# 2024-SS-ZT-2.net
KiCad netlist of a schematic drawn in EasyEDA Pro
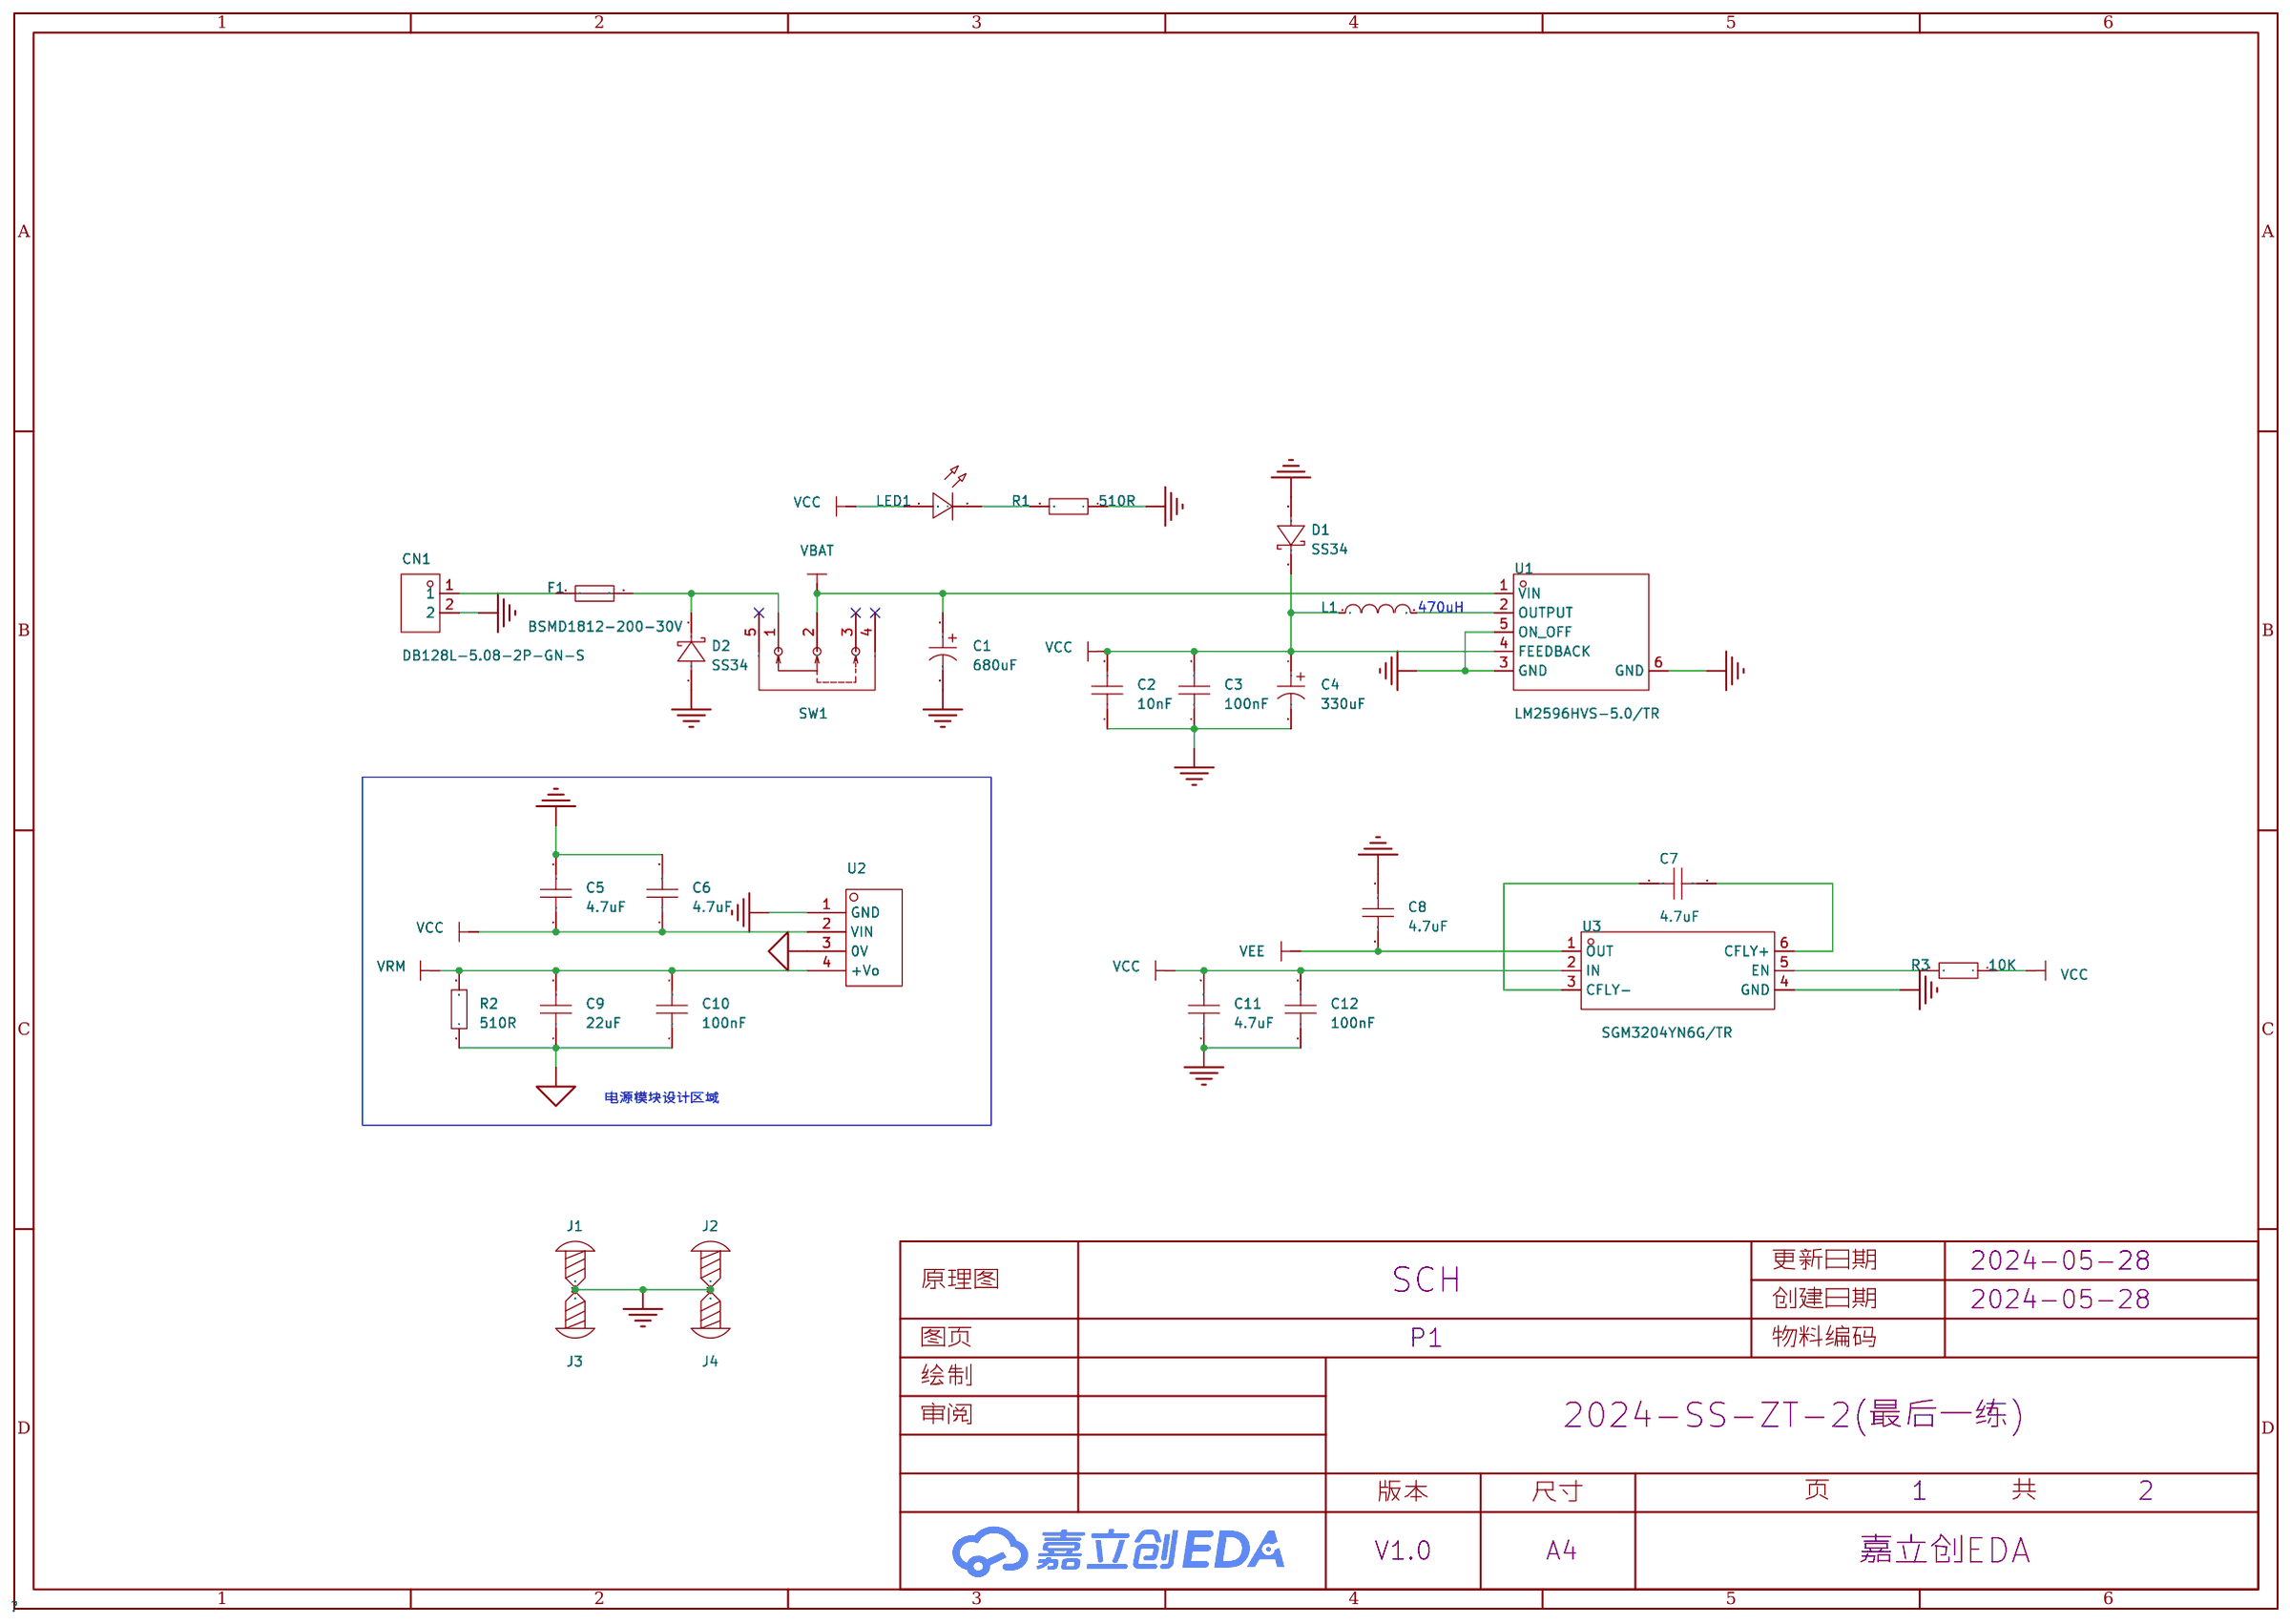
[diagram p0: P1]
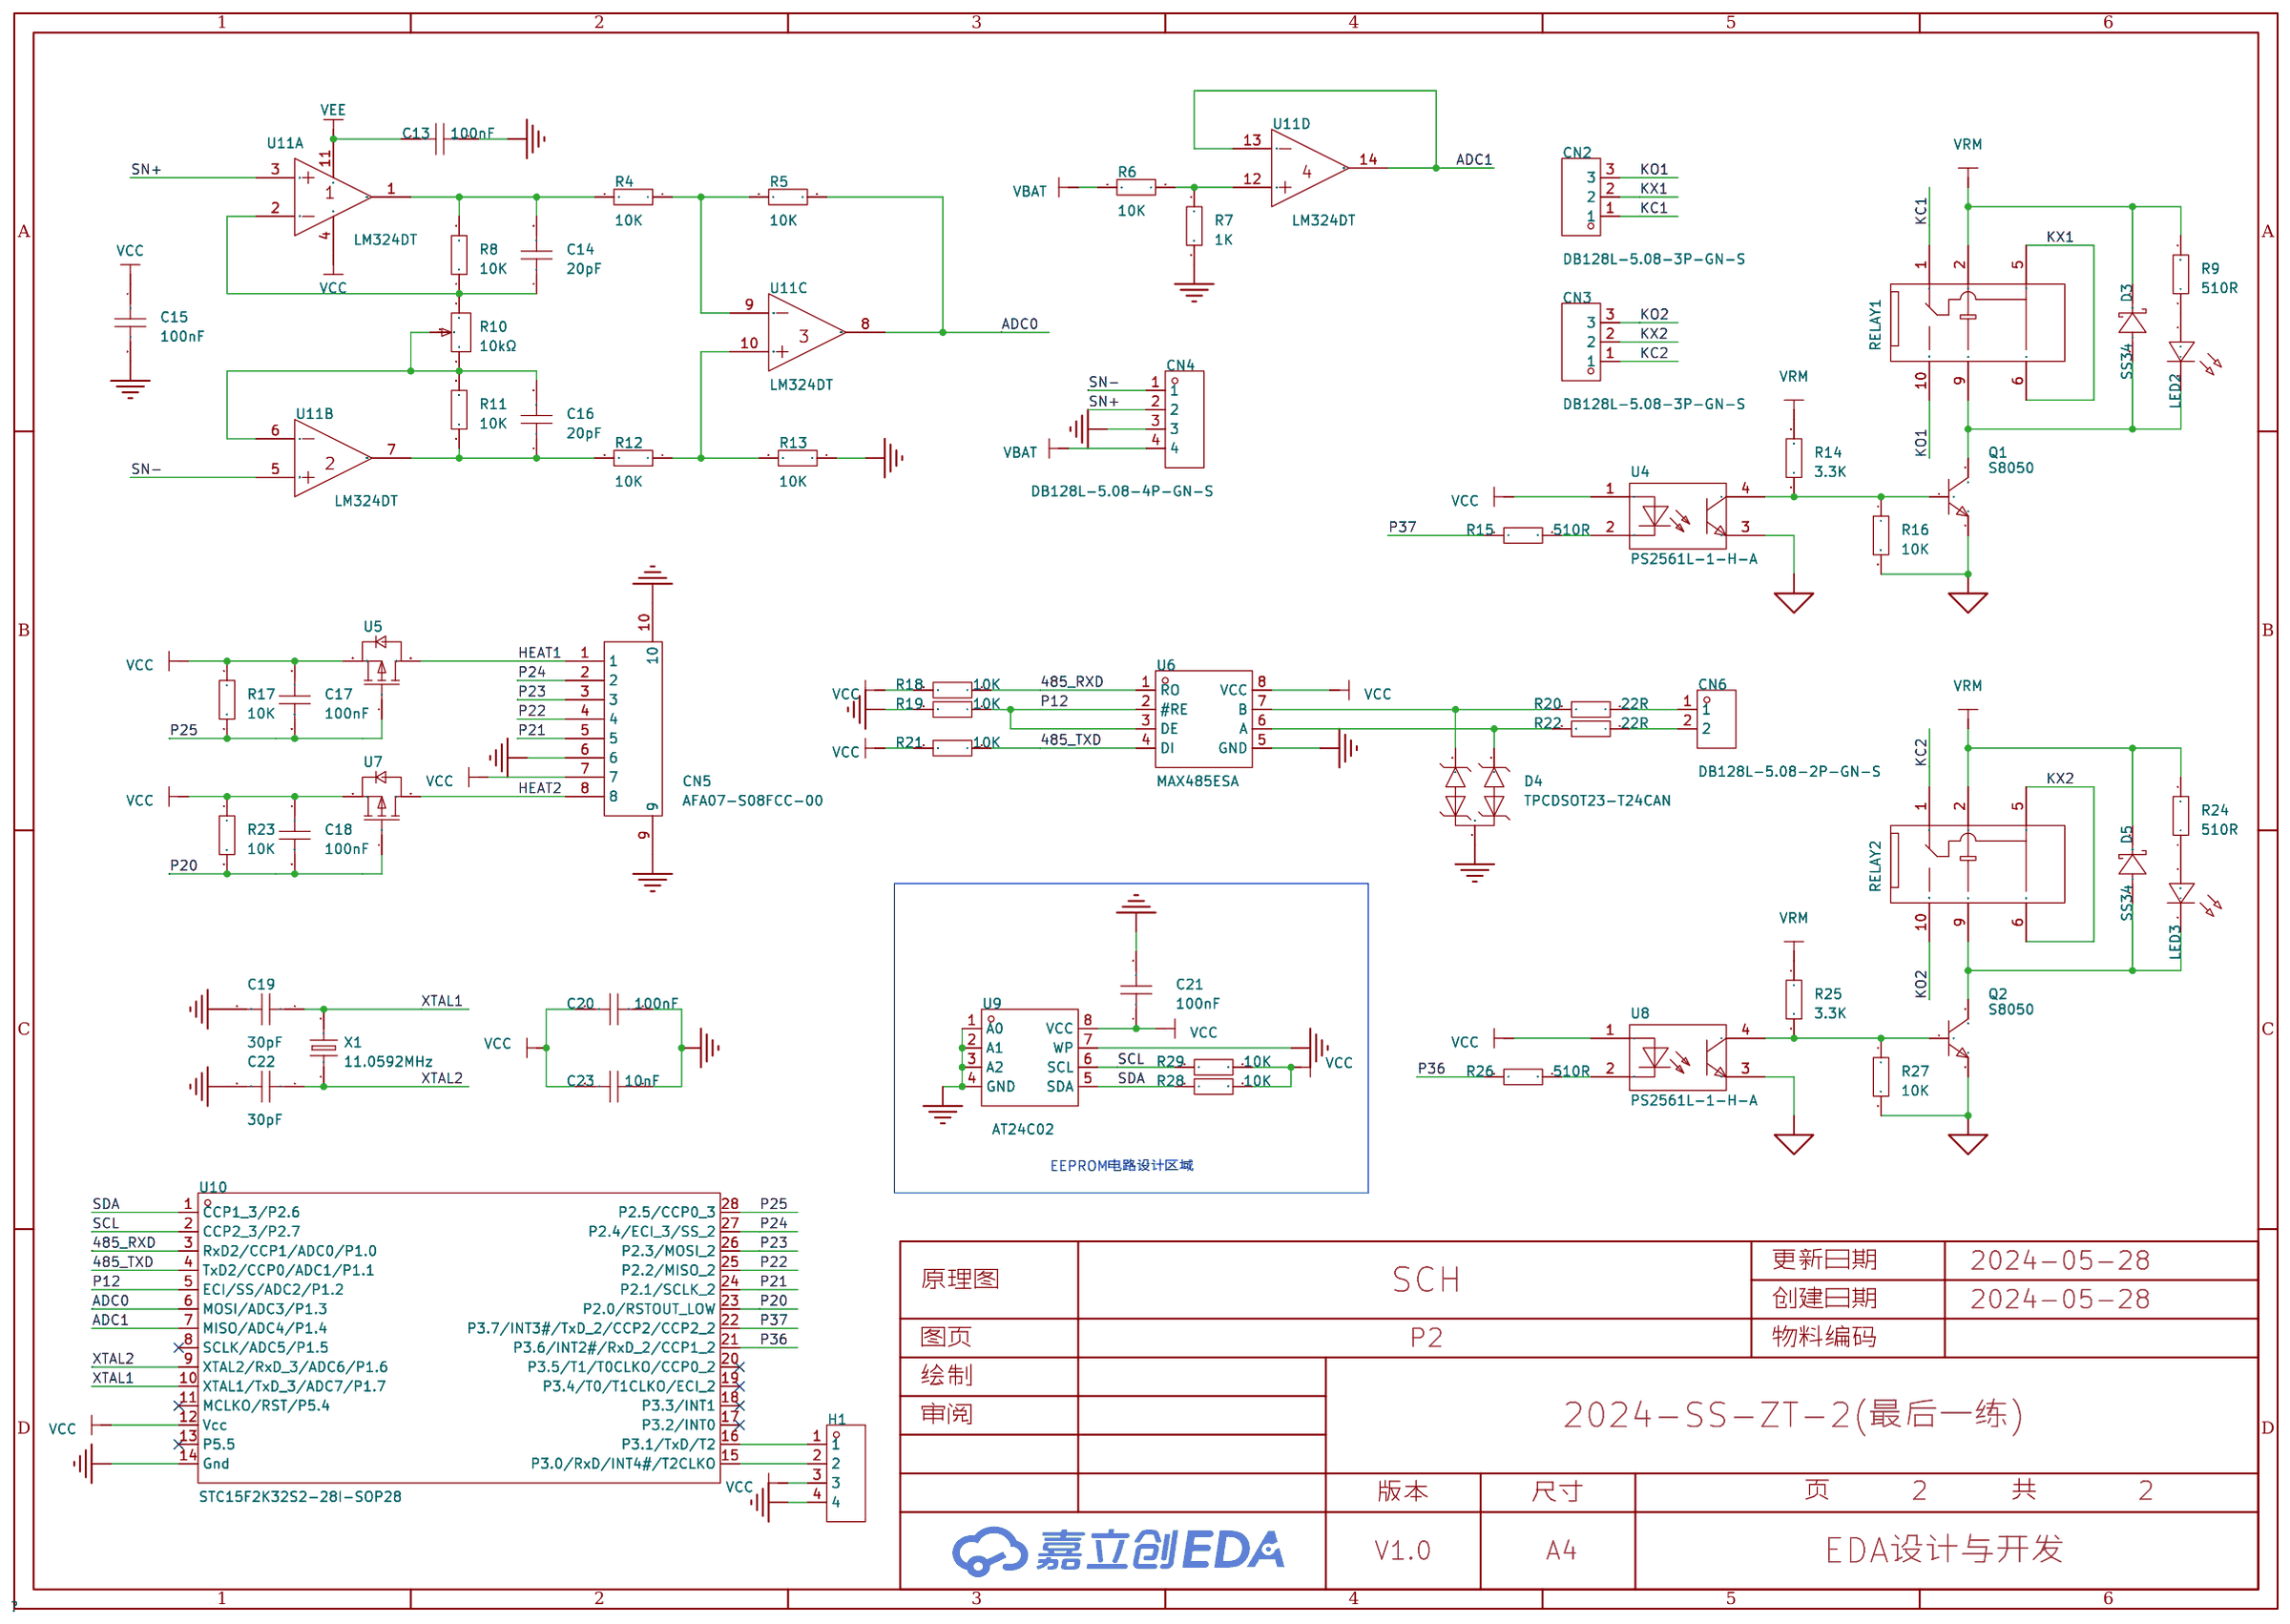
[diagram p1: P2]

(export (version "E")
  (design (tool "Eeschema 10.0.6"))
  (components
    (comp (ref "C1")
      (value "680uF")
      (footprint "easyedapro:CAP-SMD_BD10.0-L10.3-W10.3-LS11.3-FD")
      (description "容值:680uF;精度:±20%;额定电压:35V;纹波电流:380mA;")
      (fields (field (name "Manufacturer Part") "126RV0105") (field (name "Manufacturer") "KNSCHA(科尼盛)"))
      (libsource (lib "easyedapro") (part "126RV0105"))
    )
    (comp (ref "C2")
      (value "10nF")
      (footprint "easyedapro:C0805")
      (libsource (lib "easyedapro") (part "CapAcitance"))
    )
    (comp (ref "C3")
      (value "100nF")
      (footprint "easyedapro:C0805")
      (libsource (lib "easyedapro") (part "CapAcitance"))
    )
    (comp (ref "C4")
      (value "330uF")
      (footprint "easyedapro:CAP-SMD_BD6.3-L6.6-W6.6-LS7.6-RD")
      (description "容值:330uF;精度:±20%;额定电压:16V;纹波电流:170mA;")
      (fields (field (name "Manufacturer Part") "126RV0107") (field (name "Manufacturer") "KNSCHA(科尼盛)"))
      (libsource (lib "easyedapro") (part "126RV0107"))
    )
    (comp (ref "C5")
      (value "4.7uF")
      (footprint "easyedapro:C1206")
      (description "容值:22uF;精度:±10%;额定电压:16V;材质(温度系数):X5R;")
      (fields
        (field (name "Manufacturer Part") "CL31A226KOHNNNE")
        (field (name "Manufacturer") "SAMSUNG(三星)")
      )
      (libsource (lib "easyedapro") (part "CL31A226KOHNNNE"))
    )
    (comp (ref "C6")
      (value "4.7uF")
      (footprint "easyedapro:C1206")
      (description "容值:22uF;精度:±10%;额定电压:16V;材质(温度系数):X5R;")
      (fields
        (field (name "Manufacturer Part") "CL31A226KOHNNNE")
        (field (name "Manufacturer") "SAMSUNG(三星)")
      )
      (libsource (lib "easyedapro") (part "CL31A226KOHNNNE"))
    )
    (comp (ref "C7")
      (value "4.7uF")
      (footprint "easyedapro:C1206")
      (description "容值:22uF;精度:±10%;额定电压:16V;材质(温度系数):X5R;")
      (fields
        (field (name "Manufacturer Part") "CL31A226KOHNNNE")
        (field (name "Manufacturer") "SAMSUNG(三星)")
      )
      (libsource (lib "easyedapro") (part "CL31A226KOHNNNE"))
    )
    (comp (ref "C8")
      (value "4.7uF")
      (footprint "easyedapro:C1206")
      (description "容值:22uF;精度:±10%;额定电压:16V;材质(温度系数):X5R;")
      (fields
        (field (name "Manufacturer Part") "CL31A226KOHNNNE")
        (field (name "Manufacturer") "SAMSUNG(三星)")
      )
      (libsource (lib "easyedapro") (part "CL31A226KOHNNNE"))
    )
    (comp (ref "C9")
      (value "22uF")
      (footprint "easyedapro:C1206")
      (description "容值:22uF;精度:±10%;额定电压:16V;材质(温度系数):X5R;")
      (fields
        (field (name "Manufacturer Part") "CL31A226KOHNNNE")
        (field (name "Manufacturer") "SAMSUNG(三星)")
      )
      (libsource (lib "easyedapro") (part "CL31A226KOHNNNE"))
    )
    (comp (ref "C10")
      (value "100nF")
      (footprint "easyedapro:C0805")
      (libsource (lib "easyedapro") (part "CapAcitance"))
    )
    (comp (ref "C11")
      (value "4.7uF")
      (footprint "easyedapro:C1206")
      (description "容值:22uF;精度:±10%;额定电压:16V;材质(温度系数):X5R;")
      (fields
        (field (name "Manufacturer Part") "CL31A226KOHNNNE")
        (field (name "Manufacturer") "SAMSUNG(三星)")
      )
      (libsource (lib "easyedapro") (part "CL31A226KOHNNNE"))
    )
    (comp (ref "C12")
      (value "100nF")
      (footprint "easyedapro:C0805")
      (libsource (lib "easyedapro") (part "CapAcitance"))
    )
    (comp (ref "CN1")
      (value "DB128L-5.08-2P-GN-S")
      (footprint "easyedapro:CONN-TH_2P-P5.08_DB128L-5.08-2P")
      (fields (field (name "Manufacturer") "DORABO(地博电气)"))
      (libsource (lib "easyedapro") (part "DB128L-5.08-2P"))
    )
    (comp (ref "D1")
      (value "SS34")
      (footprint "easyedapro:SMA_L4.3-W2.5-LS5.0-RD")
      (description "二极管配置:独立式;正向压降(Vf):550mV@3A;直流反向耐压(Vr):40V;平均整流电流(Io):3A;")
      (fields (field (name "Manufacturer") "TWGMC(台湾迪嘉)"))
      (libsource (lib "easyedapro") (part "SS34_C727060"))
    )
    (comp (ref "D2")
      (value "SS34")
      (footprint "easyedapro:SMA_L4.3-W2.5-LS5.0-RD")
      (description "二极管配置:独立式;正向压降(Vf):550mV@3A;直流反向耐压(Vr):40V;平均整流电流(Io):3A;")
      (fields (field (name "Manufacturer") "TWGMC(台湾迪嘉)"))
      (libsource (lib "easyedapro") (part "SS34_C727060"))
    )
    (comp (ref "F1")
      (value "BSMD1812-200-30V")
      (footprint "easyedapro:F1812")
      (description "最大电压:30V;最大电流:40A;保持电流:2A;跳闸电流:4A;")
      (fields (field (name "Manufacturer") "BHFUSE(佰宏)"))
      (libsource (lib "easyedapro") (part "BSMD1812-200-30V"))
    )
    (comp (ref "J1") (value "~") (footprint "easyedapro:M2螺丝") (libsource (lib "easyedapro") (part "螺丝孔")))
    (comp (ref "J2") (value "~") (footprint "easyedapro:M2螺丝") (libsource (lib "easyedapro") (part "螺丝孔")))
    (comp (ref "J3") (value "~") (footprint "easyedapro:M2螺丝") (libsource (lib "easyedapro") (part "螺丝孔")))
    (comp (ref "J4") (value "~") (footprint "easyedapro:M2螺丝") (libsource (lib "easyedapro") (part "螺丝孔")))
    (comp (ref "L1")
      (value "470uH")
      (footprint "easyedapro:IND-SMD_L12.0-W12.0_YPRH120X")
      (description "电感值:470uH;精度:±20%;额定电流:1.06A;")
      (fields (field (name "Manufacturer Part") "YPRH1209-471M") (field (name "Manufacturer") "YJYCOIN(益嘉源)"))
      (libsource (lib "easyedapro") (part "YPRH1209-471M"))
    )
    (comp (ref "LED1")
      (value "~")
      (footprint "easyedapro:LED_TH-3mm")
      (libsource (lib "easyedapro") (part "LED_TH-R"))
    )
    (comp (ref "R1") (value "510R") (footprint "easyedapro:R0805") (libsource (lib "easyedapro") (part "电阻")))
    (comp (ref "R2") (value "510R") (footprint "easyedapro:R0805") (libsource (lib "easyedapro") (part "电阻")))
    (comp (ref "R3") (value "10K") (footprint "easyedapro:R0805") (libsource (lib "easyedapro") (part "电阻")))
    (comp (ref "SW1")
      (value "SK12D07VG4")
      (footprint "easyedapro:SW-TH_SK12D07VG4")
      (description "电路结构:单刀双掷;安装方式:侧插;额定电流(DC):500mA;额定电压(DC):50V;额定电流(AC):-;额定电压(AC):-;机械寿命:5千次;")
      (fields (field (name "Manufacturer") "SHOU HAN(首韩)"))
      (libsource (lib "easyedapro") (part "SK12D07VG4"))
    )
    (comp (ref "U1")
      (value "LM2596HVS-5.0/TR")
      (footprint "easyedapro:TO-263-5_L10.2-W8.9-P1.70-LS15.2-BR")
      (fields (field (name "Manufacturer") "HGSEMI(华冠)"))
      (libsource (lib "easyedapro") (part "LM2596HVS-5.0/TR"))
    )
    (comp (ref "U2")
      (value "~")
      (footprint "easyedapro:TH_PCON")
      (libsource (lib "easyedapro") (part "PCON"))
    )
    (comp (ref "U3")
      (value "SGM3204YN6G/TR")
      (footprint "easyedapro:SOT-23-6_L2.9-W1.6-P0.95-LS2.8-BR")
      (description "功能类型:-;输入电压:1.4V~5.5V;输出电压:-5.5V~-1.4V;输出电流(最大值):200mA;")
      (fields (field (name "Manufacturer") "SGMICRO(圣邦微)"))
      (libsource (lib "easyedapro") (part "SGM3204YN6G/TR"))
    )
    (comp (ref "C13")
      (value "100nF")
      (footprint "easyedapro:C0805")
      (libsource (lib "easyedapro") (part "CapAcitance"))
    )
    (comp (ref "C14")
      (value "20pF")
      (footprint "easyedapro:C0805")
      (libsource (lib "easyedapro") (part "CapAcitance"))
    )
    (comp (ref "C15")
      (value "100nF")
      (footprint "easyedapro:C0805")
      (libsource (lib "easyedapro") (part "CapAcitance"))
    )
    (comp (ref "C16")
      (value "20pF")
      (footprint "easyedapro:C0805")
      (libsource (lib "easyedapro") (part "CapAcitance"))
    )
    (comp (ref "C17")
      (value "100nF")
      (footprint "easyedapro:C0805")
      (libsource (lib "easyedapro") (part "CapAcitance"))
    )
    (comp (ref "C18")
      (value "100nF")
      (footprint "easyedapro:C0805")
      (libsource (lib "easyedapro") (part "CapAcitance"))
    )
    (comp (ref "C19")
      (value "30pF")
      (footprint "easyedapro:C0805")
      (libsource (lib "easyedapro") (part "CapAcitance"))
    )
    (comp (ref "C20")
      (value "100nF")
      (footprint "easyedapro:C0805")
      (libsource (lib "easyedapro") (part "CapAcitance"))
    )
    (comp (ref "C21")
      (value "100nF")
      (footprint "easyedapro:C0805")
      (libsource (lib "easyedapro") (part "CapAcitance"))
    )
    (comp (ref "C22")
      (value "30pF")
      (footprint "easyedapro:C0805")
      (libsource (lib "easyedapro") (part "CapAcitance"))
    )
    (comp (ref "C23")
      (value "10nF")
      (footprint "easyedapro:C0805")
      (libsource (lib "easyedapro") (part "CapAcitance"))
    )
    (comp (ref "CN2")
      (value "DB128L-5.08-3P-GN-S")
      (footprint "easyedapro:CONN-TH_DB128L-5.08-3P")
      (fields (field (name "Manufacturer") "DORABO(地博电气)"))
      (libsource (lib "easyedapro") (part "DB128L-5.08-3P"))
    )
    (comp (ref "CN3")
      (value "DB128L-5.08-3P-GN-S")
      (footprint "easyedapro:CONN-TH_DB128L-5.08-3P")
      (fields (field (name "Manufacturer") "DORABO(地博电气)"))
      (libsource (lib "easyedapro") (part "DB128L-5.08-3P"))
    )
    (comp (ref "CN4")
      (value "DB128L-5.08-4P-GN-S")
      (footprint "easyedapro:CONN-TH_4P_DB128L-5.08-4P-GN-S")
      (fields (field (name "Manufacturer") "DORABO(地博电气)"))
      (libsource (lib "easyedapro") (part "DB128L-5.08-4P-GN-S"))
    )
    (comp (ref "CN5")
      (value "AFA07-S08FCC-00")
      (footprint "easyedapro:FPC-SMD_P1.00-8P_LCS-XJ-H2.5")
      (description "锁定特性:抽屉式;触点类型:下接;触点数量:8P;间距:1mm;安装类型:卧贴;")
      (fields (field (name "Manufacturer") "JS(钜硕电子)"))
      (libsource (lib "easyedapro") (part "AFA07-S08FCC-00"))
    )
    (comp (ref "CN6")
      (value "DB128L-5.08-2P-GN-S")
      (footprint "easyedapro:CONN-TH_2P-P5.08_DB128L-5.08-2P")
      (fields (field (name "Manufacturer") "DORABO(地博电气)"))
      (libsource (lib "easyedapro") (part "DB128L-5.08-2P"))
    )
    (comp (ref "D3")
      (value "SS34")
      (footprint "easyedapro:SMA_L4.3-W2.5-LS5.0-RD")
      (description "二极管配置:独立式;正向压降(Vf):550mV@3A;直流反向耐压(Vr):40V;平均整流电流(Io):3A;")
      (fields (field (name "Manufacturer") "TWGMC(台湾迪嘉)"))
      (libsource (lib "easyedapro") (part "SS34_C727060"))
    )
    (comp (ref "D4")
      (value "TPCDSOT23-T24CAN")
      (footprint "easyedapro:SOT-23-3_L2.9-W1.3-P1.90-LS2.4-BR")
      (fields (field (name "Manufacturer") "TECH PUBLIC(台舟)"))
      (libsource (lib "easyedapro") (part "TPCDSOT23-T24CAN"))
    )
    (comp (ref "D5")
      (value "SS34")
      (footprint "easyedapro:SMA_L4.3-W2.5-LS5.0-RD")
      (description "二极管配置:独立式;正向压降(Vf):550mV@3A;直流反向耐压(Vr):40V;平均整流电流(Io):3A;")
      (fields (field (name "Manufacturer") "TWGMC(台湾迪嘉)"))
      (libsource (lib "easyedapro") (part "SS34_C727060"))
    )
    (comp (ref "H1")
      (value "~")
      (footprint "easyedapro:HDR-TH_4P-P2.54-V-F")
      (libsource (lib "easyedapro") (part "2.54-1*4P母"))
    )
    (comp (ref "LED2")
      (value "~")
      (footprint "easyedapro:LED_TH-3mm")
      (libsource (lib "easyedapro") (part "LED_TH-G"))
    )
    (comp (ref "LED3")
      (value "~")
      (footprint "easyedapro:LED_TH-3mm")
      (libsource (lib "easyedapro") (part "LED_TH-G"))
    )
    (comp (ref "Q1")
      (value "S8050")
      (footprint "easyedapro:SOT-23-3_L2.9-W1.3-P1.90-LS2.4-BR")
      (description "晶体管类型:NPN;集电极电流(Ic):500mA;集射极击穿电压(Vceo):25V;功率(Pd):300mW;")
      (fields (field (name "Manufacturer") "YONGYUTAI(永裕泰)"))
      (libsource (lib "easyedapro") (part "S8050_C2891804"))
    )
    (comp (ref "Q2")
      (value "S8050")
      (footprint "easyedapro:SOT-23-3_L2.9-W1.3-P1.90-LS2.4-BR")
      (description "晶体管类型:NPN;集电极电流(Ic):500mA;集射极击穿电压(Vceo):25V;功率(Pd):300mW;")
      (fields (field (name "Manufacturer") "YONGYUTAI(永裕泰)"))
      (libsource (lib "easyedapro") (part "S8050_C2891804"))
    )
    (comp (ref "R4") (value "10K") (footprint "easyedapro:R0805") (libsource (lib "easyedapro") (part "电阻")))
    (comp (ref "R5") (value "10K") (footprint "easyedapro:R0805") (libsource (lib "easyedapro") (part "电阻")))
    (comp (ref "R6") (value "10K") (footprint "easyedapro:R0805") (libsource (lib "easyedapro") (part "电阻")))
    (comp (ref "R7") (value "1K") (footprint "easyedapro:R0805") (libsource (lib "easyedapro") (part "电阻")))
    (comp (ref "R8") (value "10K") (footprint "easyedapro:R0805") (libsource (lib "easyedapro") (part "电阻")))
    (comp (ref "R9") (value "510R") (footprint "easyedapro:R0805") (libsource (lib "easyedapro") (part "电阻")))
    (comp (ref "R10")
      (value "10kΩ")
      (footprint "easyedapro:RES-ADJ-TH_3P-L10.0-W10.0-P2.50-BL-BS")
      (description "阻值:20kΩ;精度:±10%;功率:500mW;温度系数:±100ppm/°C;")
      (fields (field (name "Manufacturer Part") "3296W-1-203LF") (field (name "Manufacturer") "BOURNS"))
      (libsource (lib "easyedapro") (part "3296W-1-203LF"))
    )
    (comp (ref "R11") (value "10K") (footprint "easyedapro:R0805") (libsource (lib "easyedapro") (part "电阻")))
    (comp (ref "R12") (value "10K") (footprint "easyedapro:R0805") (libsource (lib "easyedapro") (part "电阻")))
    (comp (ref "R13") (value "10K") (footprint "easyedapro:R0805") (libsource (lib "easyedapro") (part "电阻")))
    (comp (ref "R14")
      (value "3.3K")
      (footprint "easyedapro:R0805")
      (libsource (lib "easyedapro") (part "电阻"))
    )
    (comp (ref "R15")
      (value "510R")
      (footprint "easyedapro:R0805")
      (libsource (lib "easyedapro") (part "电阻"))
    )
    (comp (ref "R16") (value "10K") (footprint "easyedapro:R0805") (libsource (lib "easyedapro") (part "电阻")))
    (comp (ref "R17") (value "10K") (footprint "easyedapro:R0805") (libsource (lib "easyedapro") (part "电阻")))
    (comp (ref "R18") (value "10K") (footprint "easyedapro:R0805") (libsource (lib "easyedapro") (part "电阻")))
    (comp (ref "R19") (value "10K") (footprint "easyedapro:R0805") (libsource (lib "easyedapro") (part "电阻")))
    (comp (ref "R20") (value "22R") (footprint "easyedapro:R0805") (libsource (lib "easyedapro") (part "电阻")))
    (comp (ref "R21") (value "10K") (footprint "easyedapro:R0805") (libsource (lib "easyedapro") (part "电阻")))
    (comp (ref "R22") (value "22R") (footprint "easyedapro:R0805") (libsource (lib "easyedapro") (part "电阻")))
    (comp (ref "R23") (value "10K") (footprint "easyedapro:R0805") (libsource (lib "easyedapro") (part "电阻")))
    (comp (ref "R24")
      (value "510R")
      (footprint "easyedapro:R0805")
      (libsource (lib "easyedapro") (part "电阻"))
    )
    (comp (ref "R25")
      (value "3.3K")
      (footprint "easyedapro:R0805")
      (libsource (lib "easyedapro") (part "电阻"))
    )
    (comp (ref "R26")
      (value "510R")
      (footprint "easyedapro:R0805")
      (libsource (lib "easyedapro") (part "电阻"))
    )
    (comp (ref "R27") (value "10K") (footprint "easyedapro:R0805") (libsource (lib "easyedapro") (part "电阻")))
    (comp (ref "R28") (value "10K") (footprint "easyedapro:R0805") (libsource (lib "easyedapro") (part "电阻")))
    (comp (ref "R29") (value "10K") (footprint "easyedapro:R0805") (libsource (lib "easyedapro") (part "电阻")))
    (comp (ref "RELAY1")
      (value "G5V-1 DC5")
      (footprint "easyedapro:RELAY-TH_G5V-1")
      (description "线圈电压:5V;触点形式:一组转换:1C(单刀双掷-转换);触点容量(电阻负载):-;最大切换电压:125V@AC；60V@DC;最大切换电流:1A;")
      (fields (field (name "Manufacturer") "OMRON(欧姆龙)"))
      (libsource (lib "easyedapro") (part "G5V-1-5VDC"))
    )
    (comp (ref "RELAY2")
      (value "G5V-1 DC5")
      (footprint "easyedapro:RELAY-TH_G5V-1")
      (description "线圈电压:5V;触点形式:一组转换:1C(单刀双掷-转换);触点容量(电阻负载):-;最大切换电压:125V@AC；60V@DC;最大切换电流:1A;")
      (fields (field (name "Manufacturer") "OMRON(欧姆龙)"))
      (libsource (lib "easyedapro") (part "G5V-1-5VDC"))
    )
    (comp (ref "U4")
      (value "PS2561L-1-H-A")
      (footprint "easyedapro:SOP-4_L6.5-W4.6-P2.54-LS9.6-TL")
      (fields (field (name "Manufacturer") "California Eastern Laboratories"))
      (libsource (lib "easyedapro") (part "PS2561L-1-H-A"))
    )
    (comp (ref "U5")
      (value "SI2301-ZE")
      (footprint "easyedapro:SOT-23-3_L2.9-W1.3-P1.90-LS2.4-BR")
      (fields (field (name "Manufacturer") "HXY MOSFET(华轩阳电子)"))
      (libsource (lib "easyedapro") (part "SI2301-ZE"))
    )
    (comp (ref "U6")
      (value "MAX485ESA")
      (footprint "easyedapro:SOP-8_L5.0-W4.0-P1.27-LS6.0-BL")
      (fields (field (name "Manufacturer") "UMW(友台半导体)"))
      (libsource (lib "easyedapro") (part "MAX485EAS"))
    )
    (comp (ref "U7")
      (value "SI2301-ZE")
      (footprint "easyedapro:SOT-23-3_L2.9-W1.3-P1.90-LS2.4-BR")
      (fields (field (name "Manufacturer") "HXY MOSFET(华轩阳电子)"))
      (libsource (lib "easyedapro") (part "SI2301-ZE"))
    )
    (comp (ref "U8")
      (value "PS2561L-1-H-A")
      (footprint "easyedapro:SOP-4_L6.5-W4.6-P2.54-LS9.6-TL")
      (fields (field (name "Manufacturer") "California Eastern Laboratories"))
      (libsource (lib "easyedapro") (part "PS2561L-1-H-A"))
    )
    (comp (ref "U9")
      (value "AT24C02")
      (footprint "easyedapro:SOP-8_L4.9-W3.9-P1.27-LS6.0-BL")
      (description "接口类型:I2C;存储容量:2Kbit;时钟频率(fc):400kHz~1MHz;")
      (fields (field (name "Manufacturer") "HXY MOSFET(华轩阳电子)"))
      (libsource (lib "easyedapro") (part "AT24C02_C7470930"))
    )
    (comp (ref "U10")
      (value "STC15F2K32S2-28I-SOP28")
      (footprint "easyedapro:SOP-28_L17.9-W7.5-P1.27-LS10.3-BL")
      (fields (field (name "Manufacturer") "STC(宏晶)"))
      (libsource (lib "easyedapro") (part "STC15F2K32S2-28I-SOP28"))
    )
    (comp (ref "U11")
      (value "LM324DT")
      (footprint "easyedapro:SOIC-14_L8.7-W3.9-P1.27-LS6.0-BL")
      (description "放大器数:四路;增益带宽积(GBP):1.3MHz;输入偏置电流(Ib):20nA;压摆率(SR):0.4V/us;带宽(-3db):-;")
      (fields (field (name "Manufacturer") "ST(意法半导体)"))
      (libsource (lib "easyedapro") (part "LM324DT"))
    )
    (comp (ref "X1")
      (value "11.0592MHz")
      (footprint "easyedapro:HC-49US_L11.5-W4.5-P4.88")
      (description "晶振类型:直插晶振;频率:11.0592MHz;常温频差:±30ppm;外接负载电容:20pF;频率稳定度(全温):±30ppm;")
      (fields
        (field (name "Manufacturer Part") "TAXD11.0592M2GLFBET2T")
        (field (name "Manufacturer") "YJX(雅晶鑫)")
      )
      (libsource (lib "easyedapro") (part "HC-49S11.0592MHZ20PF30PPM"))
    )
  )
  (nets
    (net (code "1") (name "0") (class "Default")
      (node (ref "C10") (pin "1") (pinfunction "1_1") (pintype "input"))
      (node (ref "C9") (pin "1") (pinfunction "1_1") (pintype "unspecified"))
      (node (ref "Q1") (pin "2") (pinfunction "E_2") (pintype "unspecified"))
      (node (ref "Q2") (pin "2") (pinfunction "E_2") (pintype "unspecified"))
      (node (ref "R16") (pin "2") (pinfunction "2_2") (pintype "input"))
      (node (ref "R2") (pin "1") (pinfunction "1_1") (pintype "input"))
      (node (ref "R27") (pin "2") (pinfunction "2_2") (pintype "input"))
      (node (ref "U2") (pin "3") (pinfunction "0V_3") (pintype "input"))
      (node (ref "U4") (pin "3") (pinfunction "3_3") (pintype "input"))
      (node (ref "U8") (pin "3") (pinfunction "3_3") (pintype "input"))
    )
    (net (code "2") (name "485_RXD") (class "Default")
      (node (ref "R18") (pin "1") (pinfunction "1_1") (pintype "input"))
      (node (ref "U10") (pin "3") (pinfunction "RxD2/CCP1/ADC0/P1.0_3") (pintype "input"))
      (node (ref "U6") (pin "1") (pinfunction "RO_1") (pintype "unspecified"))
    )
    (net (code "3") (name "485_TXD") (class "Default")
      (node (ref "R21") (pin "1") (pinfunction "1_1") (pintype "input"))
      (node (ref "U10") (pin "4") (pinfunction "TxD2/CCP0/ADC1/P1.1_4") (pintype "input"))
      (node (ref "U6") (pin "4") (pinfunction "DI_4") (pintype "unspecified"))
    )
    (net (code "4") (name "ADC0") (class "Default")
      (node (ref "R5") (pin "1") (pinfunction "1_1") (pintype "input"))
      (node (ref "U10") (pin "6") (pinfunction "MOSI/ADC3/P1.3_6") (pintype "input"))
      (node (ref "U11") (pin "8") (pinfunction "OUT3_8") (pintype "unspecified"))
    )
    (net (code "5") (name "ADC1") (class "Default")
      (node (ref "U10") (pin "7") (pinfunction "MISO/ADC4/P1.4_7") (pintype "input"))
      (node (ref "U11") (pin "13") (pinfunction "IN4-_13") (pintype "unspecified"))
      (node (ref "U11") (pin "14") (pinfunction "OUT4_14") (pintype "unspecified"))
    )
    (net (code "6") (name "GND") (class "Default")
      (node (ref "C1") (pin "2") (pinfunction "2_2") (pintype "input"))
      (node (ref "C11") (pin "1") (pinfunction "1_1") (pintype "unspecified"))
      (node (ref "C12") (pin "1") (pinfunction "1_1") (pintype "input"))
      (node (ref "C13") (pin "1") (pinfunction "1_1") (pintype "input"))
      (node (ref "C15") (pin "2") (pinfunction "2_2") (pintype "input"))
      (node (ref "C19") (pin "2") (pinfunction "2_2") (pintype "input"))
      (node (ref "C2") (pin "1") (pinfunction "1_1") (pintype "input"))
      (node (ref "C20") (pin "1") (pinfunction "1_1") (pintype "input"))
      (node (ref "C21") (pin "2") (pinfunction "2_2") (pintype "input"))
      (node (ref "C22") (pin "2") (pinfunction "2_2") (pintype "input"))
      (node (ref "C23") (pin "1") (pinfunction "1_1") (pintype "input"))
      (node (ref "C3") (pin "1") (pinfunction "1_1") (pintype "input"))
      (node (ref "C4") (pin "2") (pinfunction "2_2") (pintype "input"))
      (node (ref "C5") (pin "2") (pinfunction "2_2") (pintype "unspecified"))
      (node (ref "C6") (pin "2") (pinfunction "2_2") (pintype "unspecified"))
      (node (ref "C8") (pin "1") (pinfunction "1_1") (pintype "unspecified"))
      (node (ref "CN1") (pin "2") (pinfunction "2_2") (pintype "unspecified"))
      (node (ref "CN4") (pin "3") (pinfunction "3_3") (pintype "unspecified"))
      (node (ref "CN5") (pin "10") (pinfunction "10_10") (pintype "unspecified"))
      (node (ref "CN5") (pin "6") (pinfunction "6_6") (pintype "unspecified"))
      (node (ref "CN5") (pin "9") (pinfunction "9_9") (pintype "unspecified"))
      (node (ref "D1") (pin "2") (pinfunction "A_2") (pintype "unspecified"))
      (node (ref "D2") (pin "2") (pinfunction "A_2") (pintype "unspecified"))
      (node (ref "D4") (pin "3") (pinfunction "3_3") (pintype "unspecified"))
      (node (ref "H1") (pin "4") (pinfunction "4_4") (pintype "unspecified"))
      (node (ref "J1") (pin "1") (pinfunction "1_1") (pintype "input"))
      (node (ref "J2") (pin "1") (pinfunction "1_1") (pintype "input"))
      (node (ref "J3") (pin "1") (pinfunction "1_1") (pintype "input"))
      (node (ref "J4") (pin "1") (pinfunction "1_1") (pintype "input"))
      (node (ref "R1") (pin "1") (pinfunction "1_1") (pintype "input"))
      (node (ref "R13") (pin "1") (pinfunction "1_1") (pintype "input"))
      (node (ref "R19") (pin "2") (pinfunction "2_2") (pintype "input"))
      (node (ref "R7") (pin "2") (pinfunction "2_2") (pintype "input"))
      (node (ref "U1") (pin "3") (pinfunction "GND_3") (pintype "input"))
      (node (ref "U1") (pin "5") (pinfunction "ON_OFF_5") (pintype "input"))
      (node (ref "U1") (pin "6") (pinfunction "GND_6") (pintype "input"))
      (node (ref "U10") (pin "14") (pinfunction "Gnd_14") (pintype "input"))
      (node (ref "U2") (pin "1") (pinfunction "GND_1") (pintype "input"))
      (node (ref "U3") (pin "4") (pinfunction "GND_4") (pintype "unspecified"))
      (node (ref "U6") (pin "5") (pinfunction "GND_5") (pintype "unspecified"))
      (node (ref "U9") (pin "1") (pinfunction "A0_1") (pintype "unspecified"))
      (node (ref "U9") (pin "2") (pinfunction "A1_2") (pintype "unspecified"))
      (node (ref "U9") (pin "3") (pinfunction "A2_3") (pintype "unspecified"))
      (node (ref "U9") (pin "4") (pinfunction "GND_4") (pintype "unspecified"))
      (node (ref "U9") (pin "7") (pinfunction "WP_7") (pintype "unspecified"))
    )
    (net (code "7") (name "HEAT1") (class "Default")
      (node (ref "CN5") (pin "1") (pinfunction "1_1") (pintype "unspecified"))
      (node (ref "U5") (pin "3") (pinfunction "D_3") (pintype "unspecified"))
    )
    (net (code "8") (name "HEAT2") (class "Default")
      (node (ref "CN5") (pin "8") (pinfunction "8_8") (pintype "unspecified"))
      (node (ref "U7") (pin "3") (pinfunction "D_3") (pintype "unspecified"))
    )
    (net (code "9") (name "KC1") (class "Default")
      (node (ref "CN2") (pin "1") (pinfunction "1_1") (pintype "unspecified"))
      (node (ref "RELAY1") (pin "1") (pinfunction "1_1") (pintype "input"))
    )
    (net (code "10") (name "KC2") (class "Default")
      (node (ref "CN3") (pin "1") (pinfunction "1_1") (pintype "unspecified"))
      (node (ref "RELAY2") (pin "1") (pinfunction "1_1") (pintype "input"))
    )
    (net (code "11") (name "KO1") (class "Default")
      (node (ref "CN2") (pin "3") (pinfunction "3_3") (pintype "unspecified"))
      (node (ref "RELAY1") (pin "10") (pinfunction "10_10") (pintype "input"))
    )
    (net (code "12") (name "KO2") (class "Default")
      (node (ref "CN3") (pin "3") (pinfunction "3_3") (pintype "unspecified"))
      (node (ref "RELAY2") (pin "10") (pinfunction "10_10") (pintype "input"))
    )
    (net (code "13") (name "KX1") (class "Default")
      (node (ref "CN2") (pin "2") (pinfunction "2_2") (pintype "unspecified"))
      (node (ref "RELAY1") (pin "5") (pinfunction "5_5") (pintype "input"))
      (node (ref "RELAY1") (pin "6") (pinfunction "6_6") (pintype "input"))
    )
    (net (code "14") (name "KX2") (class "Default")
      (node (ref "CN3") (pin "2") (pinfunction "2_2") (pintype "unspecified"))
      (node (ref "RELAY2") (pin "5") (pinfunction "5_5") (pintype "input"))
      (node (ref "RELAY2") (pin "6") (pinfunction "6_6") (pintype "input"))
    )
    (net (code "15") (name "Net-(CN1-Pad1)") (class "Default")
      (node (ref "CN1") (pin "1") (pinfunction "1_1") (pintype "unspecified"))
      (node (ref "F1") (pin "1") (pinfunction "1_1") (pintype "unspecified"))
    )
    (net (code "16") (name "Net-(CN6-Pad1)") (class "Default")
      (node (ref "CN6") (pin "1") (pinfunction "1_1") (pintype "unspecified"))
      (node (ref "R20") (pin "1") (pinfunction "1_1") (pintype "input"))
    )
    (net (code "17") (name "Net-(CN6-Pad2)") (class "Default")
      (node (ref "CN6") (pin "2") (pinfunction "2_2") (pintype "unspecified"))
      (node (ref "R22") (pin "1") (pinfunction "1_1") (pintype "input"))
    )
    (net (code "18") (name "Net-(D2-C)") (class "Default")
      (node (ref "D2") (pin "1") (pinfunction "C_1") (pintype "unspecified"))
      (node (ref "F1") (pin "2") (pinfunction "2_2") (pintype "unspecified"))
      (node (ref "SW1") (pin "1") (pinfunction "1_1") (pintype "unspecified"))
    )
    (net (code "19") (name "Net-(D3-A)") (class "Default")
      (node (ref "D3") (pin "2") (pinfunction "A_2") (pintype "unspecified"))
      (node (ref "LED2") (pin "2") (pinfunction "A_2") (pintype "input"))
      (node (ref "Q1") (pin "3") (pinfunction "C_3") (pintype "unspecified"))
      (node (ref "RELAY1") (pin "9") (pinfunction "9_9") (pintype "input"))
    )
    (net (code "20") (name "Net-(D5-A)") (class "Default")
      (node (ref "D5") (pin "2") (pinfunction "A_2") (pintype "unspecified"))
      (node (ref "LED3") (pin "2") (pinfunction "A_2") (pintype "input"))
      (node (ref "Q2") (pin "3") (pinfunction "C_3") (pintype "unspecified"))
      (node (ref "RELAY2") (pin "9") (pinfunction "9_9") (pintype "input"))
    )
    (net (code "21") (name "Net-(LED1-A)") (class "Default")
      (node (ref "LED1") (pin "2") (pinfunction "A_2") (pintype "input"))
      (node (ref "R1") (pin "2") (pinfunction "2_2") (pintype "input"))
    )
    (net (code "22") (name "Net-(LED2-C)") (class "Default")
      (node (ref "LED2") (pin "1") (pinfunction "C_1") (pintype "input"))
      (node (ref "R9") (pin "1") (pinfunction "1_1") (pintype "input"))
    )
    (net (code "23") (name "Net-(LED3-C)") (class "Default")
      (node (ref "LED3") (pin "1") (pinfunction "C_1") (pintype "input"))
      (node (ref "R24") (pin "1") (pinfunction "1_1") (pintype "input"))
    )
    (net (code "24") (name "Net-(Q1-B)") (class "Default")
      (node (ref "Q1") (pin "1") (pinfunction "B_1") (pintype "unspecified"))
      (node (ref "R14") (pin "2") (pinfunction "2_2") (pintype "input"))
      (node (ref "R16") (pin "1") (pinfunction "1_1") (pintype "input"))
      (node (ref "U4") (pin "4") (pinfunction "4_4") (pintype "input"))
    )
    (net (code "25") (name "Net-(Q2-B)") (class "Default")
      (node (ref "Q2") (pin "1") (pinfunction "B_1") (pintype "unspecified"))
      (node (ref "R25") (pin "2") (pinfunction "2_2") (pintype "input"))
      (node (ref "R27") (pin "1") (pinfunction "1_1") (pintype "input"))
      (node (ref "U8") (pin "4") (pinfunction "4_4") (pintype "input"))
    )
    (net (code "26") (name "Net-(R15-Pad2)") (class "Default")
      (node (ref "R15") (pin "2") (pinfunction "2_2") (pintype "input"))
      (node (ref "U4") (pin "2") (pinfunction "2_2") (pintype "input"))
    )
    (net (code "27") (name "Net-(R26-Pad2)") (class "Default")
      (node (ref "R26") (pin "2") (pinfunction "2_2") (pintype "input"))
      (node (ref "U8") (pin "2") (pinfunction "2_2") (pintype "input"))
    )
    (net (code "28") (name "Net-(U1-OUTPUT)") (class "Default")
      (node (ref "L1") (pin "2") (pinfunction "2_2") (pintype "unspecified"))
      (node (ref "U1") (pin "2") (pinfunction "OUTPUT_2") (pintype "input"))
    )
    (net (code "29") (name "Net-(U3-CFLY+)") (class "Default")
      (node (ref "C7") (pin "2") (pinfunction "2_2") (pintype "unspecified"))
      (node (ref "U3") (pin "6") (pinfunction "CFLY+_6") (pintype "unspecified"))
    )
    (net (code "30") (name "Net-(U3-CFLY-)") (class "Default")
      (node (ref "C7") (pin "1") (pinfunction "1_1") (pintype "unspecified"))
      (node (ref "U3") (pin "3") (pinfunction "CFLY-_3") (pintype "unspecified"))
    )
    (net (code "31") (name "Net-(U3-EN)") (class "Default")
      (node (ref "R3") (pin "2") (pinfunction "2_2") (pintype "input"))
      (node (ref "U3") (pin "5") (pinfunction "EN_5") (pintype "unspecified"))
    )
    (net (code "32") (name "Net-(U6-A)") (class "Default")
      (node (ref "D4") (pin "1") (pinfunction "1_1") (pintype "unspecified"))
      (node (ref "R22") (pin "2") (pinfunction "2_2") (pintype "input"))
      (node (ref "U6") (pin "6") (pinfunction "A_6") (pintype "unspecified"))
    )
    (net (code "33") (name "Net-(U6-B)") (class "Default")
      (node (ref "D4") (pin "2") (pinfunction "2_2") (pintype "unspecified"))
      (node (ref "R20") (pin "2") (pinfunction "2_2") (pintype "input"))
      (node (ref "U6") (pin "7") (pinfunction "B_7") (pintype "unspecified"))
    )
    (net (code "34") (name "Net-(U10-P3.0{slash}RxD{slash}INT4#{slash}T2CLKO)") (class "Default")
      (node (ref "H1") (pin "2") (pinfunction "2_2") (pintype "unspecified"))
      (node (ref "U10") (pin "15") (pinfunction "P3.0/RxD/INT4#/T2CLKO_15") (pintype "input"))
    )
    (net (code "35") (name "Net-(U10-P3.1{slash}TxD{slash}T2)") (class "Default")
      (node (ref "H1") (pin "1") (pinfunction "1_1") (pintype "unspecified"))
      (node (ref "U10") (pin "16") (pinfunction "P3.1/TxD/T2_16") (pintype "input"))
    )
    (net (code "36") (name "Net-(U11A-IN1-)") (class "Default")
      (node (ref "C14") (pin "1") (pinfunction "1_1") (pintype "input"))
      (node (ref "R10") (pin "1") (pinfunction "1_1") (pintype "input"))
      (node (ref "R8") (pin "1") (pinfunction "1_1") (pintype "input"))
      (node (ref "U11") (pin "2") (pinfunction "IN1-_2") (pintype "unspecified"))
    )
    (net (code "37") (name "Net-(U11A-OUT1)") (class "Default")
      (node (ref "C14") (pin "2") (pinfunction "2_2") (pintype "input"))
      (node (ref "R4") (pin "2") (pinfunction "2_2") (pintype "input"))
      (node (ref "R8") (pin "2") (pinfunction "2_2") (pintype "input"))
      (node (ref "U11") (pin "1") (pinfunction "OUT1_1") (pintype "unspecified"))
    )
    (net (code "38") (name "Net-(U11B-IN2-)") (class "Default")
      (node (ref "C16") (pin "2") (pinfunction "2_2") (pintype "input"))
      (node (ref "R10") (pin "2") (pinfunction "2_2") (pintype "input"))
      (node (ref "R10") (pin "3") (pinfunction "3_3") (pintype "input"))
      (node (ref "R11") (pin "2") (pinfunction "2_2") (pintype "input"))
      (node (ref "U11") (pin "6") (pinfunction "IN2-_6") (pintype "unspecified"))
    )
    (net (code "39") (name "Net-(U11B-OUT2)") (class "Default")
      (node (ref "C16") (pin "1") (pinfunction "1_1") (pintype "input"))
      (node (ref "R11") (pin "1") (pinfunction "1_1") (pintype "input"))
      (node (ref "R12") (pin "2") (pinfunction "2_2") (pintype "input"))
      (node (ref "U11") (pin "7") (pinfunction "OUT2_7") (pintype "unspecified"))
    )
    (net (code "40") (name "Net-(U11C-IN3+)") (class "Default")
      (node (ref "R12") (pin "1") (pinfunction "1_1") (pintype "input"))
      (node (ref "R13") (pin "2") (pinfunction "2_2") (pintype "input"))
      (node (ref "U11") (pin "10") (pinfunction "IN3+_10") (pintype "unspecified"))
    )
    (net (code "41") (name "Net-(U11C-IN3-)") (class "Default")
      (node (ref "R4") (pin "1") (pinfunction "1_1") (pintype "input"))
      (node (ref "R5") (pin "2") (pinfunction "2_2") (pintype "input"))
      (node (ref "U11") (pin "9") (pinfunction "IN3-_9") (pintype "unspecified"))
    )
    (net (code "42") (name "Net-(U11D-IN4+)") (class "Default")
      (node (ref "R6") (pin "1") (pinfunction "1_1") (pintype "input"))
      (node (ref "R7") (pin "1") (pinfunction "1_1") (pintype "input"))
      (node (ref "U11") (pin "12") (pinfunction "IN4+_12") (pintype "unspecified"))
    )
    (net (code "43") (name "P12") (class "Default")
      (node (ref "R19") (pin "1") (pinfunction "1_1") (pintype "input"))
      (node (ref "U10") (pin "5") (pinfunction "ECI/SS/ADC2/P1.2_5") (pintype "input"))
      (node (ref "U6") (pin "2") (pinfunction "#RE_2") (pintype "unspecified"))
      (node (ref "U6") (pin "3") (pinfunction "DE_3") (pintype "unspecified"))
    )
    (net (code "44") (name "P20") (class "Default")
      (node (ref "C18") (pin "2") (pinfunction "2_2") (pintype "input"))
      (node (ref "R23") (pin "2") (pinfunction "2_2") (pintype "input"))
      (node (ref "U10") (pin "23") (pinfunction "P2.0/RSTOUT_LOW_23") (pintype "input"))
      (node (ref "U7") (pin "1") (pinfunction "G_1") (pintype "unspecified"))
    )
    (net (code "45") (name "P21") (class "Default")
      (node (ref "CN5") (pin "5") (pinfunction "5_5") (pintype "unspecified"))
      (node (ref "U10") (pin "24") (pinfunction "P2.1/SCLK_2_24") (pintype "input"))
    )
    (net (code "46") (name "P22") (class "Default")
      (node (ref "CN5") (pin "4") (pinfunction "4_4") (pintype "unspecified"))
      (node (ref "U10") (pin "25") (pinfunction "P2.2/MISO_2_25") (pintype "input"))
    )
    (net (code "47") (name "P23") (class "Default")
      (node (ref "CN5") (pin "3") (pinfunction "3_3") (pintype "unspecified"))
      (node (ref "U10") (pin "26") (pinfunction "P2.3/MOSI_2_26") (pintype "input"))
    )
    (net (code "48") (name "P24") (class "Default")
      (node (ref "CN5") (pin "2") (pinfunction "2_2") (pintype "unspecified"))
      (node (ref "U10") (pin "27") (pinfunction "P2.4/ECI_3/SS_2_27") (pintype "input"))
    )
    (net (code "49") (name "P25") (class "Default")
      (node (ref "C17") (pin "2") (pinfunction "2_2") (pintype "input"))
      (node (ref "R17") (pin "2") (pinfunction "2_2") (pintype "input"))
      (node (ref "U10") (pin "28") (pinfunction "P2.5/CCP0_3_28") (pintype "input"))
      (node (ref "U5") (pin "1") (pinfunction "G_1") (pintype "unspecified"))
    )
    (net (code "50") (name "P36") (class "Default")
      (node (ref "R26") (pin "1") (pinfunction "1_1") (pintype "input"))
      (node (ref "U10") (pin "21") (pinfunction "P3.6/INT2#/RxD_2/CCP1_2_21") (pintype "input"))
    )
    (net (code "51") (name "P37") (class "Default")
      (node (ref "R15") (pin "1") (pinfunction "1_1") (pintype "input"))
      (node (ref "U10") (pin "22") (pinfunction "P3.7/INT3#/TxD_2/CCP2/CCP2_2_22") (pintype "input"))
    )
    (net (code "52") (name "SCL") (class "Default")
      (node (ref "R29") (pin "1") (pinfunction "1_1") (pintype "input"))
      (node (ref "U10") (pin "2") (pinfunction "CCP2_3/P2.7_2") (pintype "input"))
      (node (ref "U9") (pin "6") (pinfunction "SCL_6") (pintype "unspecified"))
    )
    (net (code "53") (name "SDA") (class "Default")
      (node (ref "R28") (pin "1") (pinfunction "1_1") (pintype "input"))
      (node (ref "U10") (pin "1") (pinfunction "CCP1_3/P2.6_1") (pintype "input"))
      (node (ref "U9") (pin "5") (pinfunction "SDA_5") (pintype "unspecified"))
    )
    (net (code "54") (name "SN+") (class "Default")
      (node (ref "CN4") (pin "2") (pinfunction "2_2") (pintype "unspecified"))
      (node (ref "U11") (pin "3") (pinfunction "IN1+_3") (pintype "unspecified"))
    )
    (net (code "55") (name "SN-") (class "Default")
      (node (ref "CN4") (pin "1") (pinfunction "1_1") (pintype "unspecified"))
      (node (ref "U11") (pin "5") (pinfunction "IN2+_5") (pintype "unspecified"))
    )
    (net (code "56") (name "VBAT") (class "Default")
      (node (ref "C1") (pin "1") (pinfunction "1_1") (pintype "input"))
      (node (ref "CN4") (pin "4") (pinfunction "4_4") (pintype "unspecified"))
      (node (ref "R6") (pin "2") (pinfunction "2_2") (pintype "input"))
      (node (ref "SW1") (pin "2") (pinfunction "2_2") (pintype "unspecified"))
      (node (ref "U1") (pin "1") (pinfunction "VIN_1") (pintype "input"))
    )
    (net (code "57") (name "VCC") (class "Default")
      (node (ref "C11") (pin "2") (pinfunction "2_2") (pintype "unspecified"))
      (node (ref "C12") (pin "2") (pinfunction "2_2") (pintype "input"))
      (node (ref "C15") (pin "1") (pinfunction "1_1") (pintype "input"))
      (node (ref "C17") (pin "1") (pinfunction "1_1") (pintype "input"))
      (node (ref "C18") (pin "1") (pinfunction "1_1") (pintype "input"))
      (node (ref "C2") (pin "2") (pinfunction "2_2") (pintype "input"))
      (node (ref "C20") (pin "2") (pinfunction "2_2") (pintype "input"))
      (node (ref "C21") (pin "1") (pinfunction "1_1") (pintype "input"))
      (node (ref "C23") (pin "2") (pinfunction "2_2") (pintype "input"))
      (node (ref "C3") (pin "2") (pinfunction "2_2") (pintype "input"))
      (node (ref "C4") (pin "1") (pinfunction "1_1") (pintype "input"))
      (node (ref "C5") (pin "1") (pinfunction "1_1") (pintype "unspecified"))
      (node (ref "C6") (pin "1") (pinfunction "1_1") (pintype "unspecified"))
      (node (ref "CN5") (pin "7") (pinfunction "7_7") (pintype "unspecified"))
      (node (ref "D1") (pin "1") (pinfunction "C_1") (pintype "unspecified"))
      (node (ref "H1") (pin "3") (pinfunction "3_3") (pintype "unspecified"))
      (node (ref "L1") (pin "1") (pinfunction "1_1") (pintype "unspecified"))
      (node (ref "LED1") (pin "1") (pinfunction "C_1") (pintype "input"))
      (node (ref "R17") (pin "1") (pinfunction "1_1") (pintype "input"))
      (node (ref "R18") (pin "2") (pinfunction "2_2") (pintype "input"))
      (node (ref "R21") (pin "2") (pinfunction "2_2") (pintype "input"))
      (node (ref "R23") (pin "1") (pinfunction "1_1") (pintype "input"))
      (node (ref "R28") (pin "2") (pinfunction "2_2") (pintype "input"))
      (node (ref "R29") (pin "2") (pinfunction "2_2") (pintype "input"))
      (node (ref "R3") (pin "1") (pinfunction "1_1") (pintype "input"))
      (node (ref "U1") (pin "4") (pinfunction "FEEDBACK_4") (pintype "input"))
      (node (ref "U10") (pin "12") (pinfunction "Vcc_12") (pintype "input"))
      (node (ref "U11") (pin "4") (pinfunction "VCC+_4") (pintype "unspecified"))
      (node (ref "U2") (pin "2") (pinfunction "VIN_2") (pintype "input"))
      (node (ref "U3") (pin "2") (pinfunction "IN_2") (pintype "unspecified"))
      (node (ref "U4") (pin "1") (pinfunction "1_1") (pintype "input"))
      (node (ref "U5") (pin "2") (pinfunction "S_2") (pintype "unspecified"))
      (node (ref "U6") (pin "8") (pinfunction "VCC_8") (pintype "unspecified"))
      (node (ref "U7") (pin "2") (pinfunction "S_2") (pintype "unspecified"))
      (node (ref "U8") (pin "1") (pinfunction "1_1") (pintype "input"))
      (node (ref "U9") (pin "8") (pinfunction "VCC_8") (pintype "unspecified"))
    )
    (net (code "58") (name "VEE") (class "Default")
      (node (ref "C13") (pin "2") (pinfunction "2_2") (pintype "input"))
      (node (ref "C8") (pin "2") (pinfunction "2_2") (pintype "unspecified"))
      (node (ref "U11") (pin "11") (pinfunction "VCC-_11") (pintype "unspecified"))
      (node (ref "U3") (pin "1") (pinfunction "OUT_1") (pintype "unspecified"))
    )
    (net (code "59") (name "VRM") (class "Default")
      (node (ref "C10") (pin "2") (pinfunction "2_2") (pintype "input"))
      (node (ref "C9") (pin "2") (pinfunction "2_2") (pintype "unspecified"))
      (node (ref "D3") (pin "1") (pinfunction "C_1") (pintype "unspecified"))
      (node (ref "D5") (pin "1") (pinfunction "C_1") (pintype "unspecified"))
      (node (ref "R14") (pin "1") (pinfunction "1_1") (pintype "input"))
      (node (ref "R2") (pin "2") (pinfunction "2_2") (pintype "input"))
      (node (ref "R24") (pin "2") (pinfunction "2_2") (pintype "input"))
      (node (ref "R25") (pin "1") (pinfunction "1_1") (pintype "input"))
      (node (ref "R9") (pin "2") (pinfunction "2_2") (pintype "input"))
      (node (ref "RELAY1") (pin "2") (pinfunction "2_2") (pintype "input"))
      (node (ref "RELAY2") (pin "2") (pinfunction "2_2") (pintype "input"))
      (node (ref "U2") (pin "4") (pinfunction "+Vo_4") (pintype "input"))
    )
    (net (code "60") (name "XTAL1") (class "Default")
      (node (ref "C19") (pin "1") (pinfunction "1_1") (pintype "input"))
      (node (ref "U10") (pin "10") (pinfunction "XTAL1/TxD_3/ADC7/P1.7_10") (pintype "input"))
      (node (ref "X1") (pin "2") (pinfunction "2_2") (pintype "unspecified"))
    )
    (net (code "61") (name "XTAL2") (class "Default")
      (node (ref "C22") (pin "1") (pinfunction "1_1") (pintype "input"))
      (node (ref "U10") (pin "9") (pinfunction "XTAL2/RxD_3/ADC6/P1.6_9") (pintype "input"))
      (node (ref "X1") (pin "1") (pinfunction "1_1") (pintype "unspecified"))
    )
    (net (code "62") (name "unconnected-(SW1-Pad3)") (class "Default")
      (node (ref "SW1") (pin "3") (pinfunction "3_3") (pintype "unspecified+no_connect"))
    )
    (net (code "63") (name "unconnected-(SW1-Pad4)") (class "Default")
      (node (ref "SW1") (pin "4") (pinfunction "4_4") (pintype "unspecified+no_connect"))
    )
    (net (code "64") (name "unconnected-(SW1-Pad5)") (class "Default")
      (node (ref "SW1") (pin "5") (pinfunction "5_5") (pintype "unspecified+no_connect"))
    )
    (net (code "65") (name "unconnected-(U10-MCLKO{slash}RST{slash}P5.4-Pad11)") (class "Default")
      (node (ref "U10") (pin "11") (pinfunction "MCLKO/RST/P5.4_11") (pintype "input+no_connect"))
    )
    (net (code "66") (name "unconnected-(U10-P3.2{slash}INT0-Pad17)") (class "Default")
      (node (ref "U10") (pin "17") (pinfunction "P3.2/INT0_17") (pintype "input+no_connect"))
    )
    (net (code "67") (name "unconnected-(U10-P3.3{slash}INT1-Pad18)") (class "Default")
      (node (ref "U10") (pin "18") (pinfunction "P3.3/INT1_18") (pintype "input+no_connect"))
    )
    (net (code "68") (name "unconnected-(U10-P3.4{slash}T0{slash}T1CLKO{slash}ECI_2-Pad19)") (class "Default")
      (node (ref "U10") (pin "19") (pinfunction "P3.4/T0/T1CLKO/ECI_2_19") (pintype "input+no_connect"))
    )
    (net (code "69") (name "unconnected-(U10-P3.5{slash}T1{slash}T0CLKO{slash}CCP0_2-Pad20)") (class "Default")
      (node (ref "U10") (pin "20") (pinfunction "P3.5/T1/T0CLKO/CCP0_2_20") (pintype "input+no_connect"))
    )
    (net (code "70") (name "unconnected-(U10-P5.5-Pad13)") (class "Default")
      (node (ref "U10") (pin "13") (pinfunction "P5.5_13") (pintype "input+no_connect"))
    )
    (net (code "71") (name "unconnected-(U10-SCLK{slash}ADC5{slash}P1.5-Pad8)") (class "Default")
      (node (ref "U10") (pin "8") (pinfunction "SCLK/ADC5/P1.5_8") (pintype "input+no_connect"))
    )
  )
)
